# Adafruit_ADS1115_16Bit_I2C_ADC.net
KiCad netlist of a schematic drawn in EAGLE
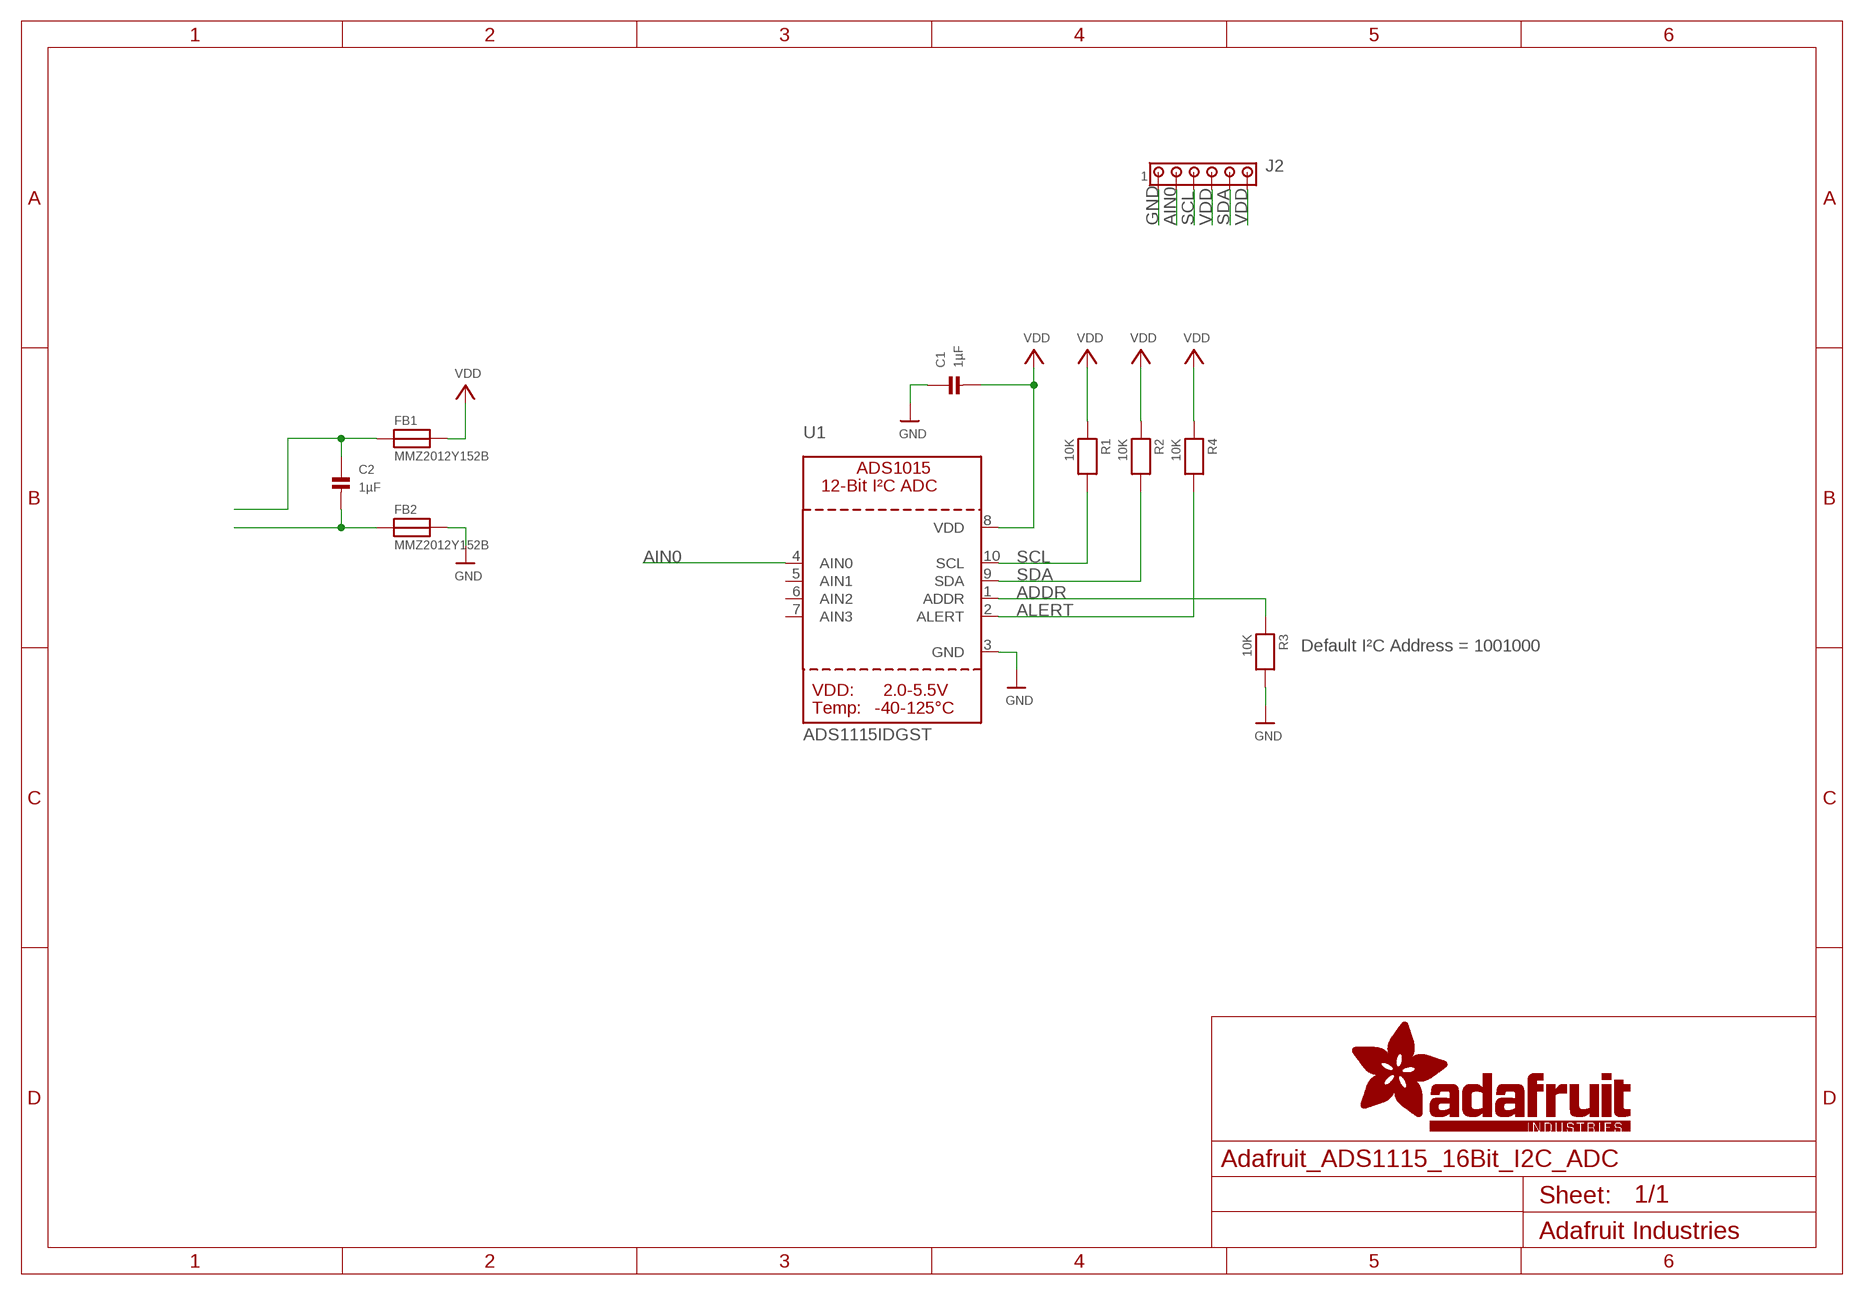
[diagram p0: schematic, sheet 1]

(export (version "E")
  (design (tool "Eeschema 10.0.6"))
  (components
    (comp (ref "C1")
      (value "1µF")
      (footprint "eagle-import:0805")
      (libsource (lib "eagle-import") (part "CAP_CERAMIC0805"))
    )
    (comp (ref "C2")
      (value "1µF")
      (footprint "eagle-import:0805")
      (libsource (lib "eagle-import") (part "CAP_CERAMIC0805"))
    )
    (comp (ref "FB1")
      (value "MMZ2012Y152B")
      (footprint "eagle-import:0805")
      (libsource (lib "eagle-import") (part "FERRITE0805"))
    )
    (comp (ref "FB2")
      (value "MMZ2012Y152B")
      (footprint "eagle-import:0805")
      (libsource (lib "eagle-import") (part "FERRITE0805"))
    )
    (comp (ref "J2")
      (value "MTA06-156")
      (footprint "eagle-import:1X6MTA")
      (libsource (lib "eagle-import") (part "MTA06-156"))
    )
    (comp (ref "R1")
      (value "10K")
      (footprint "eagle-import:0805")
      (libsource (lib "eagle-import") (part "RESISTOR0805"))
    )
    (comp (ref "R2")
      (value "10K")
      (footprint "eagle-import:0805")
      (libsource (lib "eagle-import") (part "RESISTOR0805"))
    )
    (comp (ref "R3")
      (value "10K")
      (footprint "eagle-import:0805")
      (libsource (lib "eagle-import") (part "RESISTOR0805"))
    )
    (comp (ref "R4")
      (value "10K")
      (footprint "eagle-import:0805")
      (libsource (lib "eagle-import") (part "RESISTOR0805"))
    )
    (comp (ref "U1")
      (value "ADS1115IDGST")
      (footprint "eagle-import:MSOP10")
      (libsource (lib "eagle-import") (part "ADC_ADS1015"))
    )
  )
  (nets
    (net (code "1") (name "/ADDR") (class "Default")
      (node (ref "R3") (pin "1") (pinfunction "1_1") (pintype "passive"))
      (node (ref "U1") (pin "1") (pinfunction "ADDR_1") (pintype "bidirectional"))
    )
    (net (code "2") (name "/AIN0") (class "Default")
      (node (ref "J2") (pin "2") (pinfunction "2_2") (pintype "passive"))
      (node (ref "U1") (pin "4") (pinfunction "AIN0_4") (pintype "bidirectional"))
    )
    (net (code "3") (name "/ALERT") (class "Default")
      (node (ref "R4") (pin "2") (pinfunction "2_2") (pintype "passive"))
      (node (ref "U1") (pin "2") (pinfunction "ALERT_2") (pintype "bidirectional"))
    )
    (net (code "4") (name "/SCL") (class "Default")
      (node (ref "J2") (pin "3") (pinfunction "3_3") (pintype "passive"))
      (node (ref "R1") (pin "2") (pinfunction "2_2") (pintype "passive"))
      (node (ref "U1") (pin "10") (pinfunction "SCL_10") (pintype "bidirectional"))
    )
    (net (code "5") (name "/SDA") (class "Default")
      (node (ref "J2") (pin "5") (pinfunction "5_5") (pintype "passive"))
      (node (ref "R2") (pin "2") (pinfunction "2_2") (pintype "passive"))
      (node (ref "U1") (pin "9") (pinfunction "SDA_9") (pintype "bidirectional"))
    )
    (net (code "6") (name "GND") (class "Default")
      (node (ref "C1") (pin "1") (pinfunction "P$1_1") (pintype "passive"))
      (node (ref "FB2") (pin "2") (pinfunction "P$2_2") (pintype "bidirectional"))
      (node (ref "J2") (pin "1") (pinfunction "1_1") (pintype "passive"))
      (node (ref "R3") (pin "2") (pinfunction "2_2") (pintype "passive"))
      (node (ref "U1") (pin "3") (pinfunction "GND_3") (pintype "bidirectional"))
    )
    (net (code "7") (name "Net-(C2-P$1)") (class "Default")
      (node (ref "C2") (pin "1") (pinfunction "P$1_1") (pintype "passive"))
      (node (ref "FB1") (pin "1") (pinfunction "P$1_1") (pintype "bidirectional"))
    )
    (net (code "8") (name "Net-(C2-P$2)") (class "Default")
      (node (ref "C2") (pin "2") (pinfunction "P$2_2") (pintype "passive"))
      (node (ref "FB2") (pin "1") (pinfunction "P$1_1") (pintype "bidirectional"))
    )
    (net (code "9") (name "VDD") (class "Default")
      (node (ref "C1") (pin "2") (pinfunction "P$2_2") (pintype "passive"))
      (node (ref "FB1") (pin "2") (pinfunction "P$2_2") (pintype "bidirectional"))
      (node (ref "J2") (pin "4") (pinfunction "4_4") (pintype "passive"))
      (node (ref "J2") (pin "6") (pinfunction "6_6") (pintype "passive"))
      (node (ref "R1") (pin "1") (pinfunction "1_1") (pintype "passive"))
      (node (ref "R2") (pin "1") (pinfunction "1_1") (pintype "passive"))
      (node (ref "R4") (pin "1") (pinfunction "1_1") (pintype "passive"))
      (node (ref "U1") (pin "8") (pinfunction "VDD_8") (pintype "bidirectional"))
    )
    (net (code "10") (name "unconnected-(U1-AIN1-Pad5)") (class "Default")
      (node (ref "U1") (pin "5") (pinfunction "AIN1_5") (pintype "bidirectional"))
    )
    (net (code "11") (name "unconnected-(U1-AIN2-Pad6)") (class "Default")
      (node (ref "U1") (pin "6") (pinfunction "AIN2_6") (pintype "bidirectional"))
    )
    (net (code "12") (name "unconnected-(U1-AIN3-Pad7)") (class "Default")
      (node (ref "U1") (pin "7") (pinfunction "AIN3_7") (pintype "bidirectional"))
    )
  )
)
